# XTIDA-010086_Bias_Power_Supply.net
KiCad netlist of a schematic drawn in Altium Designer
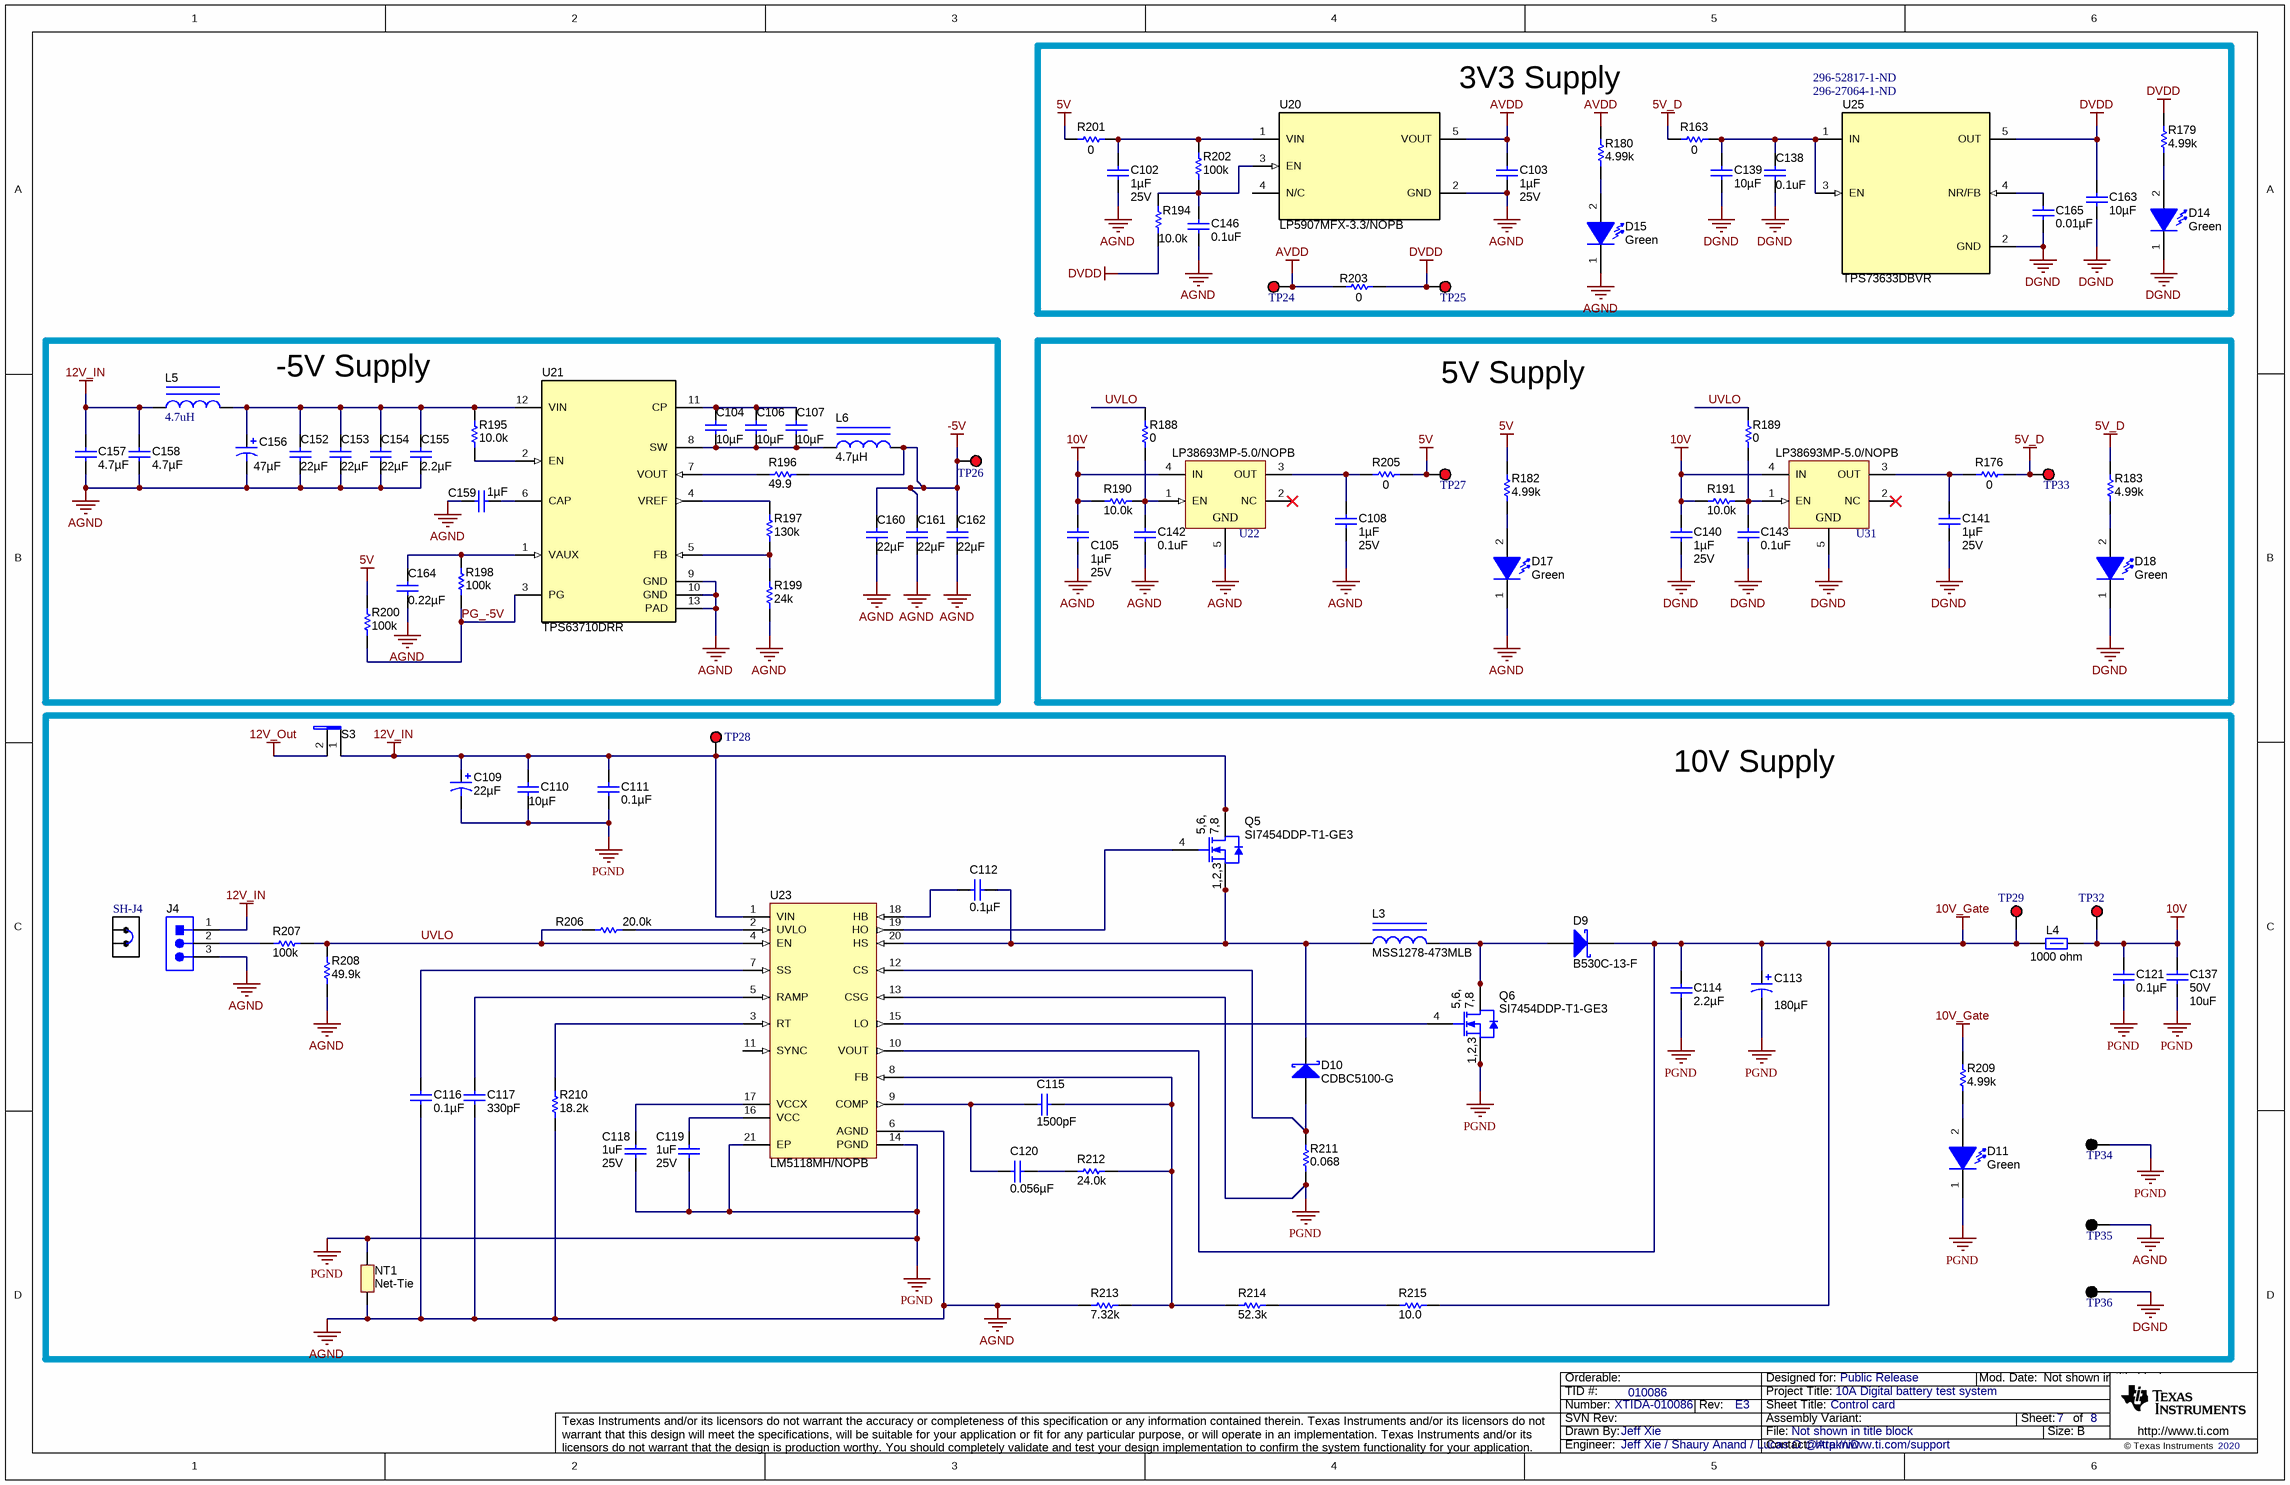
[diagram p0: XTIDA-010086_Bias Power Supply.SchDoc]

(export (version "E")
  (design (tool "Eeschema 10.0.6"))
  (components
    (comp (ref "C102")
      (value "GRM188R71E105KA12D")
      (footprint "0603")
      (description "CAP, CERM, 1 uF, 25 V, +/- 10%, X7R, 0603")
      (fields
        (field (name "MANUFACTURER") "MuRata")
        (field (name "CAP_F") "1µF")
        (field (name "VDC_V") "25V")
        (field (name "PUBLISHER") "Texas Instruments")
      )
      (libsource (lib "Capacitor_Ceramic") (part "Capacitor"))
    )
    (comp (ref "C103")
      (value "GRM188R71E105KA12D")
      (footprint "0603")
      (description "CAP, CERM, 1 uF, 25 V, +/- 10%, X7R, 0603")
      (fields
        (field (name "MANUFACTURER") "MuRata")
        (field (name "CAP_F") "1µF")
        (field (name "VDC_V") "25V")
        (field (name "PUBLISHER") "Texas Instruments")
      )
      (libsource (lib "Capacitor_Ceramic") (part "Capacitor"))
    )
    (comp (ref "C104")
      (value "EMK212BB7106MG-T")
      (footprint "0805_HV1")
      (description "CAP, CERM, 10 µF, 16 V, +/- 20%, X7R, 0805")
      (fields
        (field (name "VALUEDISPLAYED") "10µF")
        (field (name "MANUFACTURER") "Taiyo Yuden")
        (field (name "PUBLISHER") "Texas Instruments")
      )
      (libsource (lib "Capacitor_Ceramic") (part "EMK212BB7106MG-T"))
    )
    (comp (ref "C105")
      (value "GRM188R71E105KA12D")
      (footprint "0603")
      (description "CAP, CERM, 1 uF, 25 V, +/- 10%, X7R, 0603")
      (fields
        (field (name "MANUFACTURER") "MuRata")
        (field (name "CAP_F") "1µF")
        (field (name "VDC_V") "25V")
        (field (name "PUBLISHER") "Texas Instruments")
      )
      (libsource (lib "Capacitor_Ceramic") (part "Capacitor"))
    )
    (comp (ref "C106")
      (value "EMK212BB7106MG-T")
      (footprint "0805_HV1")
      (description "CAP, CERM, 10 µF, 16 V, +/- 20%, X7R, 0805")
      (fields
        (field (name "VALUEDISPLAYED") "10µF")
        (field (name "MANUFACTURER") "Taiyo Yuden")
        (field (name "PUBLISHER") "Texas Instruments")
      )
      (libsource (lib "Capacitor_Ceramic") (part "EMK212BB7106MG-T"))
    )
    (comp (ref "C107")
      (value "EMK212BB7106MG-T")
      (footprint "0805_HV1")
      (description "CAP, CERM, 10 µF, 16 V, +/- 20%, X7R, 0805")
      (fields
        (field (name "VALUEDISPLAYED") "10µF")
        (field (name "MANUFACTURER") "Taiyo Yuden")
        (field (name "PUBLISHER") "Texas Instruments")
      )
      (libsource (lib "Capacitor_Ceramic") (part "EMK212BB7106MG-T"))
    )
    (comp (ref "C108")
      (value "GRM188R71E105KA12D")
      (footprint "0603")
      (description "CAP, CERM, 1 uF, 25 V, +/- 10%, X7R, 0603")
      (fields
        (field (name "MANUFACTURER") "MuRata")
        (field (name "CAP_F") "1µF")
        (field (name "VDC_V") "25V")
        (field (name "PUBLISHER") "Texas Instruments")
      )
      (libsource (lib "Capacitor_Ceramic") (part "Capacitor"))
    )
    (comp (ref "C109")
      (value "EMVH101ADA220MJA0G")
      (footprint "CAPSMT_62_JA0")
      (description "CAP, AL, 22 µF, 100 V, +/- 20%, 0.55 ohm, SMD")
      (fields
        (field (name "VALUEDISPLAYED") "22µF")
        (field (name "MANUFACTURER") "Chemi-Con")
        (field (name "PUBLISHER") "Texas Instruments")
      )
      (libsource (lib "Capacitor_Aluminum") (part "EMVH101ADA220MJA0G"))
    )
    (comp (ref "C110")
      (value "C5750X7S2A106M230KB")
      (footprint "2220_250")
      (description "CAP, CERM, 10 µF, 100 V, +/- 20%, X7S,")
      (fields
        (field (name "VALUEDISPLAYED") "10µF")
        (field (name "MANUFACTURER") "TDK")
        (field (name "PUBLISHER") "Texas Instruments")
      )
      (libsource (lib "Capacitor_Ceramic") (part "C5750X7S2A106M230KB"))
    )
    (comp (ref "C111")
      (value "C2012X7R2A104K125AA")
      (footprint "0805_HV")
      (description "CAP, CERM, 0.1 µF, 100 V, +/- 10%, X7R, 0805")
      (fields
        (field (name "VALUEDISPLAYED") "0.1µF")
        (field (name "MANUFACTURER") "TDK")
        (field (name "PUBLISHER") "Texas Instruments")
      )
      (libsource (lib "Capacitor_Ceramic") (part "C2012X7R2A104K125AA"))
    )
    (comp (ref "C112")
      (value "GRM188R72A104KA35D")
      (footprint "0603L")
      (description "CAP, CERM, 0.1 µF, 100 V, +/- 10%, X7R, 0603")
      (fields
        (field (name "VALUEDISPLAYED") "0.1µF")
        (field (name "MANUFACTURER") "MuRata")
        (field (name "PUBLISHER") "Texas Instruments")
      )
      (libsource (lib "Capacitor_Ceramic") (part "GRM188R72A104KA35D"))
    )
    (comp (ref "C113")
      (value "APXA160ARA181MHC0G")
      (footprint "CAPSMT_62_HC0")
      (description "CAP, Aluminum Polymer, 180 µF, 16 V, +/- 20%, 0.016 ohm, HC0 SMD")
      (fields
        (field (name "VALUEDISPLAYED") "180µF")
        (field (name "MANUFACTURER") "Chemi-Con")
        (field (name "PUBLISHER") "Texas Instruments")
      )
      (libsource (lib "Capacitor_Other") (part "APXA160ARA181MHC0G"))
    )
    (comp (ref "C114")
      (value "C2012X7R1C225K125AB")
      (footprint "0805_HV")
      (description "CAP, CERM, 2.2 µF, 16 V, +/- 10%, X7R, 0805")
      (fields
        (field (name "VALUEDISPLAYED") "2.2µF")
        (field (name "MANUFACTURER") "TDK")
        (field (name "PUBLISHER") "Texas Instruments")
      )
      (libsource (lib "Capacitor_Ceramic") (part "C2012X7R1C225K125AB"))
    )
    (comp (ref "C115")
      (value "GRM1885C2A152JA01D")
      (footprint "0603L")
      (description "CAP, CERM, 1500 pF, 100 V, +/- 5%, C0G/NP0, 0603")
      (fields
        (field (name "VALUEDISPLAYED") "1500pF")
        (field (name "MANUFACTURER") "MuRata")
        (field (name "PUBLISHER") "Texas Instruments")
      )
      (libsource (lib "Capacitor_Ceramic") (part "GRM1885C2A152JA01D"))
    )
    (comp (ref "C116")
      (value "GRM188R72A104KA35D")
      (footprint "0603L")
      (description "CAP, CERM, 0.1 µF, 100 V, +/- 10%, X7R, 0603")
      (fields
        (field (name "VALUEDISPLAYED") "0.1µF")
        (field (name "MANUFACTURER") "MuRata")
        (field (name "PUBLISHER") "Texas Instruments")
      )
      (libsource (lib "Capacitor_Ceramic") (part "GRM188R72A104KA35D"))
    )
    (comp (ref "C117")
      (value "C1608C0G2A331J080AA")
      (footprint "0603L")
      (description "CAP, CERM, 330 pF, 100 V, +/- 5%, C0G/NP0, 0603")
      (fields
        (field (name "VALUEDISPLAYED") "330pF")
        (field (name "MANUFACTURER") "TDK")
        (field (name "PUBLISHER") "Texas Instruments")
      )
      (libsource (lib "Capacitor_Ceramic") (part "C1608C0G2A331J080AA"))
    )
    (comp (ref "C118")
      (value "GRM188R71E105KA12D")
      (footprint "0603")
      (description "CAP, CERM, 1 uF, 25 V, +/- 10%, X7R, 0603")
      (fields
        (field (name "VALUEDISPLAYED") "1uF")
        (field (name "MANUFACTURER") "MuRata")
        (field (name "VDC_V") "25V")
        (field (name "PUBLISHER") "Texas Instruments")
      )
      (libsource (lib "Capacitor_Ceramic") (part "Capacitor"))
    )
    (comp (ref "C119")
      (value "GRM188R71E105KA12D")
      (footprint "0603")
      (description "CAP, CERM, 1 uF, 25 V, +/- 10%, X7R, 0603")
      (fields
        (field (name "VALUEDISPLAYED") "1uF")
        (field (name "MANUFACTURER") "MuRata")
        (field (name "VDC_V") "25V")
        (field (name "PUBLISHER") "Texas Instruments")
      )
      (libsource (lib "Capacitor_Ceramic") (part "Capacitor"))
    )
    (comp (ref "C120")
      (value "GRM188R71H563KA93D")
      (footprint "0603L")
      (description "CAP, CERM, 0.056 µF, 50 V, +/- 10%, X7R, 0603")
      (fields
        (field (name "VALUEDISPLAYED") "0.056µF")
        (field (name "MANUFACTURER") "MuRata")
        (field (name "PUBLISHER") "Texas Instruments")
      )
      (libsource (lib "Capacitor_Ceramic") (part "GRM188R71H563KA93D"))
    )
    (comp (ref "C121")
      (value "C2012X7R2A104K125AA")
      (footprint "0805_HV")
      (description "CAP, CERM, 0.1 µF, 100 V, +/- 10%, X7R, 0805")
      (fields
        (field (name "VALUEDISPLAYED") "0.1µF")
        (field (name "MANUFACTURER") "TDK")
        (field (name "PUBLISHER") "Texas Instruments")
      )
      (libsource (lib "Capacitor_Ceramic") (part "C2012X7R2A104K125AA"))
    )
    (comp (ref "C137")
      (value "C3225X7R1H106M250AC")
      (footprint "1210_280")
      (description "CAP, CERM, 10 uF, 50 V, +/- 20%, X7R, 1210")
      (fields
        (field (name "MANUFACTURER") "TDK")
        (field (name "VDC_V") "50V")
        (field (name "VALUEDISPLAYED") "10uF")
        (field (name "PUBLISHER") "Texas Instruments")
      )
      (libsource (lib "TIDA-010086") (part "Capacitor"))
    )
    (comp (ref "C138")
      (value "06033C104JAT2A")
      (footprint "0603")
      (description "CAP, CERM, 0.1 uF, 25 V, +/- 5%, X7R, 0603")
      (fields
        (field (name "VALUEDISPLAYED") "0.1uF")
        (field (name "MANUFACTURER") "AVX")
        (field (name "PUBLISHER") "Texas Instruments")
      )
      (libsource (lib "TIDA-010086") (part "Capacitor"))
    )
    (comp (ref "C139")
      (value "GRM188R61E106MA73D")
      (footprint "0603")
      (description "CAP, CERM, 10 µF, 25 V,+/- 20%, X5R, 0603")
      (fields
        (field (name "VALUEDISPLAYED") "10µF")
        (field (name "MANUFACTURER") "MuRata")
        (field (name "PUBLISHER") "Texas Instruments")
      )
      (libsource (lib "Capacitor_Ceramic") (part "GRM188R61E106MA73D"))
    )
    (comp (ref "C140")
      (value "GRM188R71E105KA12D")
      (footprint "0603")
      (description "CAP, CERM, 1 uF, 25 V, +/- 10%, X7R, 0603")
      (fields
        (field (name "MANUFACTURER") "MuRata")
        (field (name "CAP_F") "1µF")
        (field (name "VDC_V") "25V")
        (field (name "PUBLISHER") "Texas Instruments")
      )
      (libsource (lib "Capacitor_Ceramic") (part "Capacitor"))
    )
    (comp (ref "C141")
      (value "GRM188R71E105KA12D")
      (footprint "0603")
      (description "CAP, CERM, 1 uF, 25 V, +/- 10%, X7R, 0603")
      (fields
        (field (name "MANUFACTURER") "MuRata")
        (field (name "CAP_F") "1µF")
        (field (name "VDC_V") "25V")
        (field (name "PUBLISHER") "Texas Instruments")
      )
      (libsource (lib "Capacitor_Ceramic") (part "Capacitor"))
    )
    (comp (ref "C142")
      (value "06033C104JAT2A")
      (footprint "0603")
      (description "CAP, CERM, 0.1 uF, 25 V, +/- 5%, X7R, 0603")
      (fields
        (field (name "VALUEDISPLAYED") "0.1uF")
        (field (name "MANUFACTURER") "AVX")
        (field (name "PUBLISHER") "Texas Instruments")
      )
      (libsource (lib "TIDA-010086") (part "Capacitor"))
    )
    (comp (ref "C143")
      (value "06033C104JAT2A")
      (footprint "0603")
      (description "CAP, CERM, 0.1 uF, 25 V, +/- 5%, X7R, 0603")
      (fields
        (field (name "VALUEDISPLAYED") "0.1uF")
        (field (name "MANUFACTURER") "AVX")
        (field (name "PUBLISHER") "Texas Instruments")
      )
      (libsource (lib "TIDA-010086") (part "Capacitor"))
    )
    (comp (ref "C146")
      (value "06033C104JAT2A")
      (footprint "0603")
      (description "CAP, CERM, 0.1 uF, 25 V, +/- 5%, X7R, 0603")
      (fields
        (field (name "VALUEDISPLAYED") "0.1uF")
        (field (name "MANUFACTURER") "AVX")
        (field (name "PUBLISHER") "Texas Instruments")
      )
      (libsource (lib "TIDA-010086") (part "Capacitor"))
    )
    (comp (ref "C152")
      (value "EMK316BB7226ML-T")
      (footprint "1206_190")
      (description "CAP, CERM, 22 µF, 16 V, +/- 20%, X7R, 1206_190")
      (fields
        (field (name "VALUEDISPLAYED") "22µF")
        (field (name "MANUFACTURER") "Taiyo Yuden")
        (field (name "PUBLISHER") "Texas Instruments")
      )
      (libsource (lib "Capacitor_Ceramic") (part "EMK316BB7226ML-T"))
    )
    (comp (ref "C153")
      (value "EMK316BB7226ML-T")
      (footprint "1206_190")
      (description "CAP, CERM, 22 µF, 16 V, +/- 20%, X7R, 1206_190")
      (fields
        (field (name "VALUEDISPLAYED") "22µF")
        (field (name "MANUFACTURER") "Taiyo Yuden")
        (field (name "PUBLISHER") "Texas Instruments")
      )
      (libsource (lib "Capacitor_Ceramic") (part "EMK316BB7226ML-T"))
    )
    (comp (ref "C154")
      (value "EMK316BB7226ML-T")
      (footprint "1206_190")
      (description "CAP, CERM, 22 µF, 16 V, +/- 20%, X7R, 1206_190")
      (fields
        (field (name "VALUEDISPLAYED") "22µF")
        (field (name "MANUFACTURER") "Taiyo Yuden")
        (field (name "PUBLISHER") "Texas Instruments")
      )
      (libsource (lib "Capacitor_Ceramic") (part "EMK316BB7226ML-T"))
    )
    (comp (ref "C155")
      (value "EMK107BB7225KA-T")
      (footprint "0603_HV")
      (description "CAP, CERM, 2.2 µF, 16 V, +/- 10%, X7R, 0603")
      (fields
        (field (name "VALUEDISPLAYED") "2.2µF")
        (field (name "MANUFACTURER") "Taiyo Yuden")
        (field (name "PUBLISHER") "Texas Instruments")
      )
      (libsource (lib "Capacitor_Ceramic") (part "EMK107BB7225KA-T"))
    )
    (comp (ref "C156")
      (value "F951C476MBAAQ2")
      (footprint "F95_B")
      (description "CAP, TA, 47 µF, 16 V, +/- 20%, 0.6 ohm, SMD")
      (fields
        (field (name "VALUEDISPLAYED") "47µF")
        (field (name "MANUFACTURER") "AVX")
        (field (name "PUBLISHER") "Texas Instruments")
      )
      (libsource (lib "Capacitor_Tantalum") (part "F951C476MBAAQ2"))
    )
    (comp (ref "C157")
      (value "GRM319R61E475KA12D")
      (footprint "1206")
      (description "CAP, CERM, 4.7 µF, 25 V,+/- 10%, X5R, 1206")
      (fields
        (field (name "VALUEDISPLAYED") "4.7µF")
        (field (name "MANUFACTURER") "MuRata")
        (field (name "PUBLISHER") "Texas Instruments")
      )
      (libsource (lib "Capacitor_Ceramic") (part "GRM319R61E475KA12D"))
    )
    (comp (ref "C158")
      (value "GRM319R61E475KA12D")
      (footprint "1206")
      (description "CAP, CERM, 4.7 µF, 25 V,+/- 10%, X5R, 1206")
      (fields
        (field (name "VALUEDISPLAYED") "4.7µF")
        (field (name "MANUFACTURER") "MuRata")
        (field (name "PUBLISHER") "Texas Instruments")
      )
      (libsource (lib "Capacitor_Ceramic") (part "GRM319R61E475KA12D"))
    )
    (comp (ref "C159")
      (value "C1005X5R1C105K050BC")
      (footprint "0402")
      (description "CAP, CERM, 1 µF, 16 V,+/- 10%, X5R, 0402")
      (fields
        (field (name "VALUEDISPLAYED") "1µF")
        (field (name "MANUFACTURER") "TDK")
        (field (name "PUBLISHER") "Texas Instruments")
      )
      (libsource (lib "Capacitor_Ceramic") (part "C1005X5R1C105K050BC"))
    )
    (comp (ref "C160")
      (value "C2012X7S1A226M125AC")
      (footprint "0805_HV1")
      (description "CAP, CERM, 22 µF, 10 V, +/- 20%, X7S, 0805")
      (fields
        (field (name "VALUEDISPLAYED") "22µF")
        (field (name "MANUFACTURER") "TDK")
        (field (name "PUBLISHER") "Texas Instruments")
      )
      (libsource (lib "Capacitor_Ceramic") (part "C2012X7S1A226M125AC"))
    )
    (comp (ref "C161")
      (value "C2012X7S1A226M125AC")
      (footprint "0805_HV1")
      (description "CAP, CERM, 22 µF, 10 V, +/- 20%, X7S, 0805")
      (fields
        (field (name "VALUEDISPLAYED") "22µF")
        (field (name "MANUFACTURER") "TDK")
        (field (name "PUBLISHER") "Texas Instruments")
      )
      (libsource (lib "Capacitor_Ceramic") (part "C2012X7S1A226M125AC"))
    )
    (comp (ref "C162")
      (value "C2012X7S1A226M125AC")
      (footprint "0805_HV1")
      (description "CAP, CERM, 22 µF, 10 V, +/- 20%, X7S, 0805")
      (fields
        (field (name "VALUEDISPLAYED") "22µF")
        (field (name "MANUFACTURER") "TDK")
        (field (name "PUBLISHER") "Texas Instruments")
      )
      (libsource (lib "Capacitor_Ceramic") (part "C2012X7S1A226M125AC"))
    )
    (comp (ref "C163")
      (value "GRM188R61E106MA73D")
      (footprint "0603")
      (description "CAP, CERM, 10 µF, 25 V,+/- 20%, X5R, 0603")
      (fields
        (field (name "VALUEDISPLAYED") "10µF")
        (field (name "MANUFACTURER") "MuRata")
        (field (name "PUBLISHER") "Texas Instruments")
      )
      (libsource (lib "Capacitor_Ceramic") (part "GRM188R61E106MA73D"))
    )
    (comp (ref "C164")
      (value "GRM155R71C224KA12D")
      (footprint "0402")
      (description "CAP, CERM, 0.22 µF, 16 V,+/- 10%, X7R, 0402")
      (fields
        (field (name "VALUEDISPLAYED") "0.22µF")
        (field (name "MANUFACTURER") "MuRata")
        (field (name "PUBLISHER") "Texas Instruments")
      )
      (libsource (lib "Capacitor_Ceramic") (part "GRM155R71C224KA12D"))
    )
    (comp (ref "C165")
      (value "06031C103KAT2A")
      (footprint "0603")
      (description "CAP, CERM, 0.01 µF, 100 V, +/- 10%, X7R, 0603")
      (fields
        (field (name "VALUEDISPLAYED") "0.01µF")
        (field (name "MANUFACTURER") "AVX")
        (field (name "PUBLISHER") "Texas Instruments")
      )
      (libsource (lib "Capacitor_Ceramic") (part "06031C103KAT2A"))
    )
    (comp (ref "D9")
      (value "B530C-13-F")
      (footprint "SMC")
      (description "Diode, Schottky, 30 V, 5 A, SMC")
      (fields (field (name "MANUFACTURER") "Diodes Inc.") (field (name "PUBLISHER") "Texas Instruments"))
      (libsource (lib "Diode") (part "B530C-13-F"))
    )
    (comp (ref "D10")
      (value "CDBC5100-G")
      (footprint "SMC")
      (description "Diode, Schottky, 100 V, 5 A, SMC")
      (fields
        (field (name "MANUFACTURER") "Comchip Technology")
        (field (name "PUBLISHER") "Texas Instruments")
      )
      (libsource (lib "Diode") (part "CDBC5100-G"))
    )
    (comp (ref "D11")
      (value "Green")
      (footprint "WL-SMCW_GREEN")
      (description "LED, Green, SMD")
      (fields
        (field (name "MANUFACTURER") "Wurth Elektronik")
        (field (name "PARTNUMBER") "150060VS75000")
        (field (name "PUBLISHER") "Texas Instruments")
      )
      (libsource (lib "LED") (part "150060VS75000"))
    )
    (comp (ref "D14")
      (value "Green")
      (footprint "WL-SMCW_GREEN")
      (description "LED, Green, SMD")
      (fields
        (field (name "MANUFACTURER") "Wurth Elektronik")
        (field (name "PARTNUMBER") "150060VS75000")
        (field (name "PUBLISHER") "Texas Instruments")
      )
      (libsource (lib "LED") (part "150060VS75000"))
    )
    (comp (ref "D15")
      (value "Green")
      (footprint "WL-SMCW_GREEN")
      (description "LED, Green, SMD")
      (fields
        (field (name "MANUFACTURER") "Wurth Elektronik")
        (field (name "PARTNUMBER") "150060VS75000")
        (field (name "PUBLISHER") "Texas Instruments")
      )
      (libsource (lib "LED") (part "150060VS75000"))
    )
    (comp (ref "D17")
      (value "Green")
      (footprint "WL-SMCW_GREEN")
      (description "LED, Green, SMD")
      (fields
        (field (name "MANUFACTURER") "Wurth Elektronik")
        (field (name "PARTNUMBER") "150060VS75000")
        (field (name "PUBLISHER") "Texas Instruments")
      )
      (libsource (lib "LED") (part "150060VS75000"))
    )
    (comp (ref "D18")
      (value "Green")
      (footprint "WL-SMCW_GREEN")
      (description "LED, Green, SMD")
      (fields
        (field (name "MANUFACTURER") "Wurth Elektronik")
        (field (name "PARTNUMBER") "150060VS75000")
        (field (name "PUBLISHER") "Texas Instruments")
      )
      (libsource (lib "LED") (part "150060VS75000"))
    )
    (comp (ref "J4")
      (value "0022284033")
      (footprint "Molex_0022284033")
      (description "Header, 2.54mm, 3x1, Tin, TH")
      (fields
        (field (name "MANUFACTURER") "Molex")
        (field (name "SYMBOLCREATOR") "a0799628")
        (field (name "PUBLISHER") "Texas Instruments")
      )
      (libsource (lib "Connectors_Molex") (part "0022284033"))
    )
    (comp (ref "L3")
      (value "MSS1278-473MLB")
      (footprint "mss1278")
      (description "Inductor, Shielded Drum Core, Ferrite, 47 µH, 2.9 A, 0.07 ohm, SMD")
      (fields (field (name "MANUFACTURER") "Coilcraft") (field (name "PUBLISHER") "Texas Instruments"))
      (libsource (lib "TIDA-010086") (part "MSS1278-473MLB"))
    )
    (comp (ref "L4")
      (value "1000 ohm")
      (footprint "1806_HighSpeed")
      (description "Ferrite Bead, 1000 ohm @ 100 MHz, 1.5 A, 1806")
      (fields
        (field (name "MANUFACTURER") "MuRata")
        (field (name "PARTNUMBER") "BLM41PG102SN1L")
        (field (name "PUBLISHER") "Texas Instruments")
      )
      (libsource (lib "TIDA-010086") (part "CMP-0003369-1"))
    )
    (comp (ref "L5")
      (value "MAKK2016T4R7M")
      (footprint "MAKK2016")
      (description "Inductor, Wirewound, 4.7 uH, 0.95 A, 0.38 ohm, SMD")
      (fields
        (field (name "MANUFACTURER") "Taiyo Yuden")
        (field (name "VALUEDISPLAYED") "4.7uH")
        (field (name "PUBLISHER") "Texas Instruments")
      )
      (libsource (lib "TIDA-010086") (part "Inductor_Iron"))
    )
    (comp (ref "L6")
      (value "XFL4020-472MEB")
      (footprint "XFL4020")
      (description "Inductor, Shielded, Composite, 4.7 µH, 2.7 A, 0.05 ohm, SMD")
      (fields
        (field (name "VALUEDISPLAYED") "4.7µH")
        (field (name "MANUFACTURER") "Coilcraft")
        (field (name "PUBLISHER") "Texas Instruments")
      )
      (libsource (lib "TIDA-010086") (part "XFL4020-472MEB"))
    )
    (comp (ref "NT1")
      (value "Net-Tie")
      (footprint "Net-Tie_10mil")
      (description "Single point connection between nets.")
      (fields (field (name "SYMBOLCREATOR") "codlsc") (field (name "PUBLISHER") "Texas Instruments"))
      (libsource (lib "MiscParts") (part "Net-Tie"))
    )
    (comp (ref "Q5")
      (value "SI7454DDP-T1-GE3")
      (footprint "PowerPAK_SO-8")
      (description "MOSFET, N-CH, 100 V, 21 A, PowerPAK SO-8")
      (fields (field (name "MANUFACTURER") "Vishay-Siliconix") (field (name "PUBLISHER") "Texas Instruments"))
      (libsource (lib "FETs") (part "SI7454DDP-T1-GE3"))
    )
    (comp (ref "Q6")
      (value "SI7454DDP-T1-GE3")
      (footprint "PowerPAK_SO-8")
      (description "MOSFET, N-CH, 100 V, 21 A, PowerPAK SO-8")
      (fields (field (name "MANUFACTURER") "Vishay-Siliconix") (field (name "PUBLISHER") "Texas Instruments"))
      (libsource (lib "FETs") (part "SI7454DDP-T1-GE3"))
    )
    (comp (ref "R163")
      (value "CRCW06030000Z0ED")
      (footprint "0603")
      (description "RES, 0, 5%, 0.1 W, 0603")
      (fields
        (field (name "PARTNUMBER") "ERJ-3GEY0R00V")
        (field (name "MANUFACTURER") "Panasonic")
        (field (name "VALUEDISPLAYED") "0")
        (field (name "PUBLISHER") "Texas Instruments")
      )
      (libsource (lib "TIDA-010086") (part "CMP-0025874-3"))
    )
    (comp (ref "R176")
      (value "CRCW06030000Z0ED")
      (footprint "0603")
      (description "RES, 0, 5%, 0.1 W, 0603")
      (fields
        (field (name "PARTNUMBER") "ERJ-3GEY0R00V")
        (field (name "MANUFACTURER") "Panasonic")
        (field (name "VALUEDISPLAYED") "0")
        (field (name "PUBLISHER") "Texas Instruments")
      )
      (libsource (lib "TIDA-010086") (part "CMP-0025874-3"))
    )
    (comp (ref "R179")
      (value "CRCW06034K99FKEA")
      (footprint "0603L")
      (description "RES, 4.99 k, 1%, 0.1 W, 0603")
      (fields
        (field (name "VALUEDISPLAYED") "4.99k")
        (field (name "MANUFACTURER") "Vishay-Dale")
        (field (name "PUBLISHER") "Texas Instruments")
      )
      (libsource (lib "Resistor_0603") (part "CRCW06034K99FKEA"))
    )
    (comp (ref "R180")
      (value "CRCW06034K99FKEA")
      (footprint "0603L")
      (description "RES, 4.99 k, 1%, 0.1 W, 0603")
      (fields
        (field (name "VALUEDISPLAYED") "4.99k")
        (field (name "MANUFACTURER") "Vishay-Dale")
        (field (name "PUBLISHER") "Texas Instruments")
      )
      (libsource (lib "Resistor_0603") (part "CRCW06034K99FKEA"))
    )
    (comp (ref "R182")
      (value "CRCW06034K99FKEA")
      (footprint "0603L")
      (description "RES, 4.99 k, 1%, 0.1 W, 0603")
      (fields
        (field (name "VALUEDISPLAYED") "4.99k")
        (field (name "MANUFACTURER") "Vishay-Dale")
        (field (name "PUBLISHER") "Texas Instruments")
      )
      (libsource (lib "Resistor_0603") (part "CRCW06034K99FKEA"))
    )
    (comp (ref "R183")
      (value "CRCW06034K99FKEA")
      (footprint "0603L")
      (description "RES, 4.99 k, 1%, 0.1 W, 0603")
      (fields
        (field (name "VALUEDISPLAYED") "4.99k")
        (field (name "MANUFACTURER") "Vishay-Dale")
        (field (name "PUBLISHER") "Texas Instruments")
      )
      (libsource (lib "Resistor_0603") (part "CRCW06034K99FKEA"))
    )
    (comp (ref "R188")
      (value "CRCW04020000Z0ED")
      (footprint "0402")
      (description "RES, 0, 5%, 0.063 W, 0402")
      (fields
        (field (name "VALUEDISPLAYED") "0")
        (field (name "MANUFACTURER") "Vishay-Dale")
        (field (name "PUBLISHER") "Texas Instruments")
      )
      (libsource (lib "Resistor_0402") (part "CRCW04020000Z0ED"))
    )
    (comp (ref "R189")
      (value "CRCW04020000Z0ED")
      (footprint "0402")
      (description "RES, 0, 5%, 0.063 W, 0402")
      (fields
        (field (name "VALUEDISPLAYED") "0")
        (field (name "MANUFACTURER") "Vishay-Dale")
        (field (name "PUBLISHER") "Texas Instruments")
      )
      (libsource (lib "Resistor_0402") (part "CRCW04020000Z0ED"))
    )
    (comp (ref "R190")
      (value "RC0603FR-0710KL")
      (footprint "0603")
      (description "RES, 10.0 k, 1%, 0.1 W, 0603")
      (fields (field (name "MANUFACTURER") "Yageo") (field (name "VALUEDISPLAYED") "10.0k"))
      (libsource (lib "TIDA-010086") (part "Resistor"))
    )
    (comp (ref "R191")
      (value "RC0603FR-0710KL")
      (footprint "0603")
      (description "RES, 10.0 k, 1%, 0.1 W, 0603")
      (fields (field (name "MANUFACTURER") "Yageo") (field (name "VALUEDISPLAYED") "10.0k"))
      (libsource (lib "TIDA-010086") (part "Resistor"))
    )
    (comp (ref "R194")
      (value "RC0603FR-0710KL")
      (footprint "0603")
      (description "RES, 10.0 k, 1%, 0.1 W, 0603")
      (fields (field (name "MANUFACTURER") "Yageo") (field (name "VALUEDISPLAYED") "10.0k"))
      (libsource (lib "TIDA-010086") (part "Resistor"))
    )
    (comp (ref "R195")
      (value "RC0603FR-0710KL")
      (footprint "0603")
      (description "RES, 10.0 k, 1%, 0.1 W, 0603")
      (fields (field (name "MANUFACTURER") "Yageo") (field (name "VALUEDISPLAYED") "10.0k"))
      (libsource (lib "TIDA-010086") (part "Resistor"))
    )
    (comp (ref "R196")
      (value "CRCW040249R9FKED")
      (footprint "0402")
      (description "RES, 49.9, 1%, 0.063 W, 0402")
      (fields
        (field (name "VALUEDISPLAYED") "49.9")
        (field (name "MANUFACTURER") "Vishay-Dale")
        (field (name "PUBLISHER") "Texas Instruments")
      )
      (libsource (lib "Resistor_0402") (part "CRCW040249R9FKED"))
    )
    (comp (ref "R197")
      (value "CRCW0402130KFKED")
      (footprint "0402")
      (description "RES, 130 k, 1%, 0.063 W, 0402")
      (fields
        (field (name "VALUEDISPLAYED") "130k")
        (field (name "MANUFACTURER") "Vishay-Dale")
        (field (name "PUBLISHER") "Texas Instruments")
      )
      (libsource (lib "Resistor_0402") (part "CRCW0402130KFKED"))
    )
    (comp (ref "R198")
      (value "CRCW0402100KDHEDP")
      (footprint "0402")
      (description "RES, 100 k, 0.5%, 0.063 W, 0402")
      (fields
        (field (name "VALUEDISPLAYED") "100k")
        (field (name "MANUFACTURER") "Vishay-Dale")
        (field (name "PUBLISHER") "Texas Instruments")
      )
      (libsource (lib "Resistor_0402") (part "CRCW0402100KDHEDP"))
    )
    (comp (ref "R199")
      (value "CRCW040224K0JNED")
      (footprint "0402")
      (description "RES, 24 k, 5%, 0.063 W, 0402")
      (fields
        (field (name "VALUEDISPLAYED") "24k")
        (field (name "MANUFACTURER") "Vishay-Dale")
        (field (name "PUBLISHER") "Texas Instruments")
      )
      (libsource (lib "Resistor_0402") (part "CRCW040224K0JNED"))
    )
    (comp (ref "R200")
      (value "CRCW0402100KDHEDP")
      (footprint "0402")
      (description "RES, 100 k, 0.5%, 0.063 W, 0402")
      (fields
        (field (name "VALUEDISPLAYED") "100k")
        (field (name "MANUFACTURER") "Vishay-Dale")
        (field (name "PUBLISHER") "Texas Instruments")
      )
      (libsource (lib "Resistor_0402") (part "CRCW0402100KDHEDP"))
    )
    (comp (ref "R201")
      (value "CRCW06030000Z0ED")
      (footprint "0603")
      (description "RES, 0, 5%, 0.1 W, 0603")
      (fields
        (field (name "PARTNUMBER") "ERJ-3GEY0R00V")
        (field (name "MANUFACTURER") "Panasonic")
        (field (name "VALUEDISPLAYED") "0")
        (field (name "PUBLISHER") "Texas Instruments")
      )
      (libsource (lib "TIDA-010086") (part "CMP-0025874-3"))
    )
    (comp (ref "R202")
      (value "CRCW0603100KFKEA")
      (footprint "0603")
      (description "RES, 100 k, 1%, 0.1 W, 0603")
      (fields
        (field (name "MANUFACTURER") "Vishay-Dale")
        (field (name "VALUEDISPLAYED") "100k")
        (field (name "PUBLISHER") "Texas Instruments")
      )
      (libsource (lib "TIDA-010086") (part "Resistor"))
    )
    (comp (ref "R203")
      (value "CRCW06030000Z0ED")
      (footprint "0603")
      (description "RES, 0, 5%, 0.1 W, 0603")
      (fields
        (field (name "PARTNUMBER") "ERJ-3GEY0R00V")
        (field (name "MANUFACTURER") "Panasonic")
        (field (name "VALUEDISPLAYED") "0")
        (field (name "PUBLISHER") "Texas Instruments")
      )
      (libsource (lib "TIDA-010086") (part "CMP-0025874-3"))
    )
    (comp (ref "R205")
      (value "CRCW06030000Z0ED")
      (footprint "0603")
      (description "RES, 0, 5%, 0.1 W, 0603")
      (fields
        (field (name "PARTNUMBER") "ERJ-3GEY0R00V")
        (field (name "MANUFACTURER") "Panasonic")
        (field (name "VALUEDISPLAYED") "0")
        (field (name "PUBLISHER") "Texas Instruments")
      )
      (libsource (lib "TIDA-010086") (part "CMP-0025874-3"))
    )
    (comp (ref "R206")
      (value "CRCW060320K0FKEA")
      (footprint "0603L")
      (description "RES, 20.0 k, 1%, 0.1 W, 0603")
      (fields
        (field (name "VALUEDISPLAYED") "20.0k")
        (field (name "MANUFACTURER") "Vishay-Dale")
        (field (name "PUBLISHER") "Texas Instruments")
      )
      (libsource (lib "Resistor_0603") (part "CRCW060320K0FKEA"))
    )
    (comp (ref "R207")
      (value "RC0603FR-07100KL")
      (footprint "0603")
      (description "RES, 100 k, 1%, 0.1 W, 0603")
      (fields (field (name "MANUFACTURER") "Yageo") (field (name "VALUEDISPLAYED") "100k"))
      (libsource (lib "TIDA-010086") (part "Resistor"))
    )
    (comp (ref "R208")
      (value "CRCW060349K9FKEA")
      (footprint "0603")
      (description "RES, 49.9 k, 1%, 0.1 W, 0603")
      (fields
        (field (name "VALUEDISPLAYED") "49.9k")
        (field (name "MANUFACTURER") "Vishay-Dale")
        (field (name "PUBLISHER") "Texas Instruments")
      )
      (libsource (lib "Resistor_0603") (part "CRCW060349K9FKEA"))
    )
    (comp (ref "R209")
      (value "CRCW06034K99FKEA")
      (footprint "0603L")
      (description "RES, 4.99 k, 1%, 0.1 W, 0603")
      (fields
        (field (name "VALUEDISPLAYED") "4.99k")
        (field (name "MANUFACTURER") "Vishay-Dale")
        (field (name "PUBLISHER") "Texas Instruments")
      )
      (libsource (lib "Resistor_0603") (part "CRCW06034K99FKEA"))
    )
    (comp (ref "R210")
      (value "CRCW060318K2FKEA")
      (footprint "0603L")
      (description "RES, 18.2 k, 1%, 0.1 W, 0603")
      (fields
        (field (name "VALUEDISPLAYED") "18.2k")
        (field (name "MANUFACTURER") "Vishay-Dale")
        (field (name "PUBLISHER") "Texas Instruments")
      )
      (libsource (lib "Resistor_0603") (part "CRCW060318K2FKEA"))
    )
    (comp (ref "R211")
      (value "PRL1632-R068-F-T1")
      (footprint "0612")
      (description "RES, 0.068, 1%, 1 W, 0612")
      (fields
        (field (name "VALUEDISPLAYED") "0.068")
        (field (name "MANUFACTURER") "Susumu Co Ltd")
        (field (name "PUBLISHER") "Texas Instruments")
      )
      (libsource (lib "Resistor_OtherSMT") (part "PRL1632-R068-F-T1"))
    )
    (comp (ref "R212")
      (value "RC0603FR-0724KL")
      (footprint "0603L")
      (description "RES, 24.0 k, 1%, 0.1 W, 0603")
      (fields
        (field (name "VALUEDISPLAYED") "24.0k")
        (field (name "MANUFACTURER") "Yageo America")
        (field (name "PUBLISHER") "Texas Instruments")
      )
      (libsource (lib "Resistor_0603") (part "RC0603FR-0724KL"))
    )
    (comp (ref "R213")
      (value "RC0603FR-077K32L")
      (footprint "0603")
      (description "RES, 7.32 k, 1%, 0.1 W, 0603")
      (fields
        (field (name "MANUFACTURER") "Yageo America")
        (field (name "VALUEDISPLAYED") "7.32k")
        (field (name "PUBLISHER") "Texas Instruments")
      )
      (libsource (lib "TIDA-010086") (part "CMP-0023278-3"))
    )
    (comp (ref "R214")
      (value "RC0603FR-0752K3L")
      (footprint "0603")
      (description "RES, 52.3 k, 1%, 0.1 W, 0603")
      (fields
        (field (name "MANUFACTURER") "Yageo America")
        (field (name "VALUEDISPLAYED") "52.3k")
        (field (name "PUBLISHER") "Texas Instruments")
      )
      (libsource (lib "TIDA-010086") (part "CMP-0023172-3"))
    )
    (comp (ref "R215")
      (value "CRCW060310R0FKEA")
      (footprint "0603L")
      (description "RES, 10.0, 1%, 0.1 W, 0603")
      (fields
        (field (name "VALUEDISPLAYED") "10.0")
        (field (name "MANUFACTURER") "Vishay-Dale")
        (field (name "PUBLISHER") "Texas Instruments")
      )
      (libsource (lib "Resistor_0603") (part "CRCW060310R0FKEA"))
    )
    (comp (ref "S3")
      (value "L101011MS02Q")
      (footprint "SW_ L101011MS02Q")
      (description "SWITCH SLIDE SPST 4A PCB, TH")
      (fields
        (field (name "MANUFACTURER") "C&K Components")
        (field (name "SYMBOL CREATOR") "a0411947")
        (field (name "PUBLISHER") "Texas Instruments")
      )
      (libsource (lib "Switches") (part "L101011MS02Q"))
    )
    (comp (ref "SH-J4")
      (value "60900213421")
      (footprint "Wurth_60900213421")
      (description "Shunt, 2.54mm, Gold, Black")
      (fields (field (name "MANUFACTURER") "Wurth Elektronik") (field (name "PUBLISHER") "Texas Instruments"))
      (libsource (lib "Hardware") (part "60900213421"))
    )
    (comp (ref "TP24")
      (value "5000")
      (footprint "Keystone5000")
      (description "Test Point, Miniature, Red, TH")
      (fields (field (name "MANUFACTURER") "Keystone") (field (name "PUBLISHER") "Texas Instruments"))
      (libsource (lib "Connectors_Keystone") (part "5000"))
    )
    (comp (ref "TP25")
      (value "5000")
      (footprint "Keystone5000")
      (description "Test Point, Miniature, Red, TH")
      (fields (field (name "MANUFACTURER") "Keystone") (field (name "PUBLISHER") "Texas Instruments"))
      (libsource (lib "Connectors_Keystone") (part "5000"))
    )
    (comp (ref "TP26")
      (value "5000")
      (footprint "Keystone5000")
      (description "Test Point, Miniature, Red, TH")
      (fields (field (name "MANUFACTURER") "Keystone") (field (name "PUBLISHER") "Texas Instruments"))
      (libsource (lib "Connectors_Keystone") (part "5000"))
    )
    (comp (ref "TP27")
      (value "5000")
      (footprint "Keystone5000")
      (description "Test Point, Miniature, Red, TH")
      (fields (field (name "MANUFACTURER") "Keystone") (field (name "PUBLISHER") "Texas Instruments"))
      (libsource (lib "Connectors_Keystone") (part "5000"))
    )
    (comp (ref "TP28")
      (value "5000")
      (footprint "Keystone5000")
      (description "Test Point, Miniature, Red, TH")
      (fields (field (name "MANUFACTURER") "Keystone") (field (name "PUBLISHER") "Texas Instruments"))
      (libsource (lib "Connectors_Keystone") (part "5000"))
    )
    (comp (ref "TP29")
      (value "5000")
      (footprint "Keystone5000")
      (description "Test Point, Miniature, Red, TH")
      (fields (field (name "MANUFACTURER") "Keystone") (field (name "PUBLISHER") "Texas Instruments"))
      (libsource (lib "Connectors_Keystone") (part "5000"))
    )
    (comp (ref "TP32")
      (value "5000")
      (footprint "Keystone5000")
      (description "Test Point, Miniature, Red, TH")
      (fields (field (name "MANUFACTURER") "Keystone") (field (name "PUBLISHER") "Texas Instruments"))
      (libsource (lib "Connectors_Keystone") (part "5000"))
    )
    (comp (ref "TP33")
      (value "5000")
      (footprint "Keystone5000")
      (description "Test Point, Miniature, Red, TH")
      (fields (field (name "MANUFACTURER") "Keystone") (field (name "PUBLISHER") "Texas Instruments"))
      (libsource (lib "Connectors_Keystone") (part "5000"))
    )
    (comp (ref "TP34")
      (value "5001")
      (footprint "Keystone5001")
      (description "Test Point, Miniature, Black, TH")
      (fields (field (name "MANUFACTURER") "Keystone") (field (name "PUBLISHER") "Texas Instruments"))
      (libsource (lib "Connectors_Keystone") (part "5001"))
    )
    (comp (ref "TP35")
      (value "5001")
      (footprint "Keystone5001")
      (description "Test Point, Miniature, Black, TH")
      (fields (field (name "MANUFACTURER") "Keystone") (field (name "PUBLISHER") "Texas Instruments"))
      (libsource (lib "Connectors_Keystone") (part "5001"))
    )
    (comp (ref "TP36")
      (value "5001")
      (footprint "Keystone5001")
      (description "Test Point, Miniature, Black, TH")
      (fields (field (name "MANUFACTURER") "Keystone") (field (name "PUBLISHER") "Texas Instruments"))
      (libsource (lib "Connectors_Keystone") (part "5001"))
    )
    (comp (ref "U20")
      (value "LP5907MFX-3.3/NOPB")
      (footprint "DBV0005A_N")
      (description "250-mA Ultra-Low-Noise, Low-IQ LDO, DBV0005A (SOT-23-5)")
      (fields
        (field (name "MANUFACTURER") "Texas Instruments")
        (field (name "PARTNUMBER") "LP5907MFX-3.3/NOPB")
        (field (name "PUBLISHER") "Texas Instruments")
      )
      (libsource (lib "TIDA-010086") (part "LP5907"))
    )
    (comp (ref "U21")
      (value "TPS63710DRR")
      (footprint "DRR0012C")
      (description "Synchronous Inverting Buck Converter, DRR0012C")
      (fields
        (field (name "MANUFACTURER") "Texas Instruments")
        (field (name "SYMBOLCREATOR") "Altium")
        (field (name "PUBLISHER") "Texas Instruments")
      )
      (libsource (lib "TIDA-010086") (part "TPS63710DRR"))
    )
    (comp (ref "U22")
      (value "LP38693MP-5.0/NOPB")
      (footprint "NDC0005A_N")
      (fields
        (field (name "PARTNUMBER") "LP38693MP-5.0/NOPB")
        (field (name "MANUFACTURER") "Texas Instruments")
      )
      (libsource (lib "TIDA-010086") (part "PM-REG-LP38692-SOT5"))
    )
    (comp (ref "U23")
      (value "LM5118MH/NOPB")
      (footprint "MXA20A_N")
      (description "Wide Voltage Range Buck-Boost Controller, 20-pin TSSOP-EP, Pb-Free")
      (fields (field (name "MANUFACTURER") "Texas Instruments") (field (name "PUBLISHER") "Altium Limited"))
      (libsource (lib "TIDA-010086") (part "LM5118MH/NOPB"))
    )
    (comp (ref "U25")
      (value "TPS73633DBVR")
      (footprint "DBV0005A_N")
      (fields
        (field (name "PARTNUMBER") "TPS73633DBVR")
        (field (name "MANUFACTURER") "Texas Instruments")
        (field (name "ALTERNATE PARTNUMBER") "TPS73633DBVT")
        (field (name "SUPPLIER PART NUMBER 1") "296-27064-1-ND")
        (field (name "SUPPLIER PART NUMBER 2") "296-52817-1-ND")
      )
      (libsource (lib "TIDA-010086") (part "TPS736xxDBV"))
    )
    (comp (ref "U31")
      (value "LP38693MP-5.0/NOPB")
      (footprint "NDC0005A_N")
      (fields
        (field (name "PARTNUMBER") "LP38693MP-5.0/NOPB")
        (field (name "MANUFACTURER") "Texas Instruments")
      )
      (libsource (lib "TIDA-010086") (part "PM-REG-LP38692-SOT5"))
    )
  )
  (nets
    (net (code "1") (name "-5V") (class "Default")
      (node (ref "C160") (pin "1") (pinfunction "1_1") (pintype "passive"))
      (node (ref "C161") (pin "1") (pinfunction "1_1") (pintype "passive"))
      (node (ref "C162") (pin "1") (pinfunction "1_1") (pintype "passive"))
      (node (ref "L6") (pin "2") (pinfunction "2_2") (pintype "passive"))
      (node (ref "R196") (pin "1") (pinfunction "1_1") (pintype "passive"))
      (node (ref "TP26") (pin "1") (pintype "passive"))
    )
    (net (code "2") (name "/PG_-5V") (class "Default")
      (node (ref "R198") (pin "1") (pinfunction "1_1") (pintype "passive"))
      (node (ref "R200") (pin "1") (pinfunction "1_1") (pintype "passive"))
      (node (ref "U21") (pin "3") (pinfunction "PG_3") (pintype "open_collector"))
    )
    (net (code "3") (name "/UVLO") (class "Default")
      (node (ref "R188") (pin "1") (pinfunction "1_1") (pintype "passive"))
      (node (ref "R189") (pin "1") (pinfunction "1_1") (pintype "passive"))
      (node (ref "R206") (pin "1") (pinfunction "1_1") (pintype "passive"))
      (node (ref "R207") (pin "1") (pinfunction "1_1") (pintype "passive"))
      (node (ref "R208") (pin "2") (pinfunction "2_2") (pintype "passive"))
      (node (ref "U23") (pin "4") (pinfunction "EN_4") (pintype "input"))
    )
    (net (code "4") (name "5V") (class "Default")
      (node (ref "R182") (pin "1") (pinfunction "1_1") (pintype "passive"))
      (node (ref "R200") (pin "2") (pinfunction "2_2") (pintype "passive"))
      (node (ref "R201") (pin "1") (pinfunction "1_1") (pintype "passive"))
      (node (ref "R205") (pin "2") (pinfunction "2_2") (pintype "passive"))
      (node (ref "TP27") (pin "1") (pintype "passive"))
    )
    (net (code "5") (name "5V_D") (class "Default")
      (node (ref "R163") (pin "1") (pinfunction "1_1") (pintype "passive"))
      (node (ref "R176") (pin "2") (pinfunction "2_2") (pintype "passive"))
      (node (ref "R183") (pin "1") (pinfunction "1_1") (pintype "passive"))
      (node (ref "TP33") (pin "1") (pintype "passive"))
    )
    (net (code "6") (name "10V") (class "Default")
      (node (ref "C105") (pin "1") (pinfunction "1_1") (pintype "passive"))
      (node (ref "C121") (pin "1") (pinfunction "1_1") (pintype "passive"))
      (node (ref "C137") (pin "1") (pinfunction "1_1") (pintype "passive"))
      (node (ref "C140") (pin "1") (pinfunction "1_1") (pintype "passive"))
      (node (ref "L4") (pin "2") (pinfunction "2_2") (pintype "passive"))
      (node (ref "R190") (pin "2") (pinfunction "2_2") (pintype "passive"))
      (node (ref "R191") (pin "2") (pinfunction "2_2") (pintype "passive"))
      (node (ref "TP32") (pin "1") (pintype "passive"))
      (node (ref "U22") (pin "4") (pinfunction "IN_4") (pintype "power_in"))
      (node (ref "U31") (pin "4") (pinfunction "IN_4") (pintype "power_in"))
    )
    (net (code "7") (name "10V_Gate") (class "Default")
      (node (ref "C113") (pin "1") (pinfunction "+_1") (pintype "passive"))
      (node (ref "C114") (pin "1") (pinfunction "1_1") (pintype "passive"))
      (node (ref "D9") (pin "1") (pinfunction "K_1") (pintype "passive"))
      (node (ref "L4") (pin "1") (pinfunction "1_1") (pintype "passive"))
      (node (ref "R209") (pin "1") (pinfunction "1_1") (pintype "passive"))
      (node (ref "R215") (pin "2") (pinfunction "2_2") (pintype "passive"))
      (node (ref "TP29") (pin "1") (pintype "passive"))
      (node (ref "U23") (pin "10") (pinfunction "VOUT_10") (pintype "output"))
    )
    (net (code "8") (name "12V_IN") (class "Default")
      (node (ref "C109") (pin "1") (pinfunction "+_1") (pintype "passive"))
      (node (ref "C110") (pin "1") (pinfunction "1_1") (pintype "passive"))
      (node (ref "C111") (pin "1") (pinfunction "1_1") (pintype "passive"))
      (node (ref "C157") (pin "1") (pinfunction "1_1") (pintype "passive"))
      (node (ref "C158") (pin "1") (pinfunction "1_1") (pintype "passive"))
      (node (ref "J4") (pin "1") (pinfunction "1_1") (pintype "passive"))
      (node (ref "L5") (pin "1") (pinfunction "1_1") (pintype "passive"))
      (node (ref "Q5") (pin "5") (pinfunction "D_5") (pintype "passive"))
      (node (ref "Q5") (pin "6") (pinfunction "D_6") (pintype "passive"))
      (node (ref "Q5") (pin "7") (pinfunction "D_7") (pintype "passive"))
      (node (ref "Q5") (pin "8") (pinfunction "D_8") (pintype "passive"))
      (node (ref "Q5") (pin "9") (pinfunction "D_9") (pintype "passive"))
      (node (ref "S3") (pin "1") (pinfunction "1_1") (pintype "passive"))
      (node (ref "TP28") (pin "1") (pintype "passive"))
      (node (ref "U23") (pin "1") (pinfunction "VIN_1") (pintype "power_in"))
    )
    (net (code "9") (name "12V_Out") (class "Default")
      (node (ref "S3") (pin "2") (pinfunction "2_2") (pintype "passive"))
    )
    (net (code "10") (name "AGND") (class "Default")
      (node (ref "C102") (pin "2") (pinfunction "2_2") (pintype "passive"))
      (node (ref "C103") (pin "2") (pinfunction "2_2") (pintype "passive"))
      (node (ref "C105") (pin "2") (pinfunction "2_2") (pintype "passive"))
      (node (ref "C108") (pin "2") (pinfunction "2_2") (pintype "passive"))
      (node (ref "C116") (pin "2") (pinfunction "2_2") (pintype "passive"))
      (node (ref "C117") (pin "2") (pinfunction "2_2") (pintype "passive"))
      (node (ref "C142") (pin "2") (pinfunction "2_2") (pintype "passive"))
      (node (ref "C146") (pin "2") (pinfunction "2_2") (pintype "passive"))
      (node (ref "C152") (pin "2") (pinfunction "2_2") (pintype "passive"))
      (node (ref "C153") (pin "2") (pinfunction "2_2") (pintype "passive"))
      (node (ref "C154") (pin "2") (pinfunction "2_2") (pintype "passive"))
      (node (ref "C155") (pin "2") (pinfunction "2_2") (pintype "passive"))
      (node (ref "C156") (pin "2") (pinfunction "-_2") (pintype "passive"))
      (node (ref "C157") (pin "2") (pinfunction "2_2") (pintype "passive"))
      (node (ref "C158") (pin "2") (pinfunction "2_2") (pintype "passive"))
      (node (ref "C159") (pin "1") (pinfunction "1_1") (pintype "passive"))
      (node (ref "C160") (pin "2") (pinfunction "2_2") (pintype "passive"))
      (node (ref "C161") (pin "2") (pinfunction "2_2") (pintype "passive"))
      (node (ref "C162") (pin "2") (pinfunction "2_2") (pintype "passive"))
      (node (ref "C164") (pin "2") (pinfunction "2_2") (pintype "passive"))
      (node (ref "D15") (pin "1") (pinfunction "K_1") (pintype "passive"))
      (node (ref "D17") (pin "1") (pinfunction "K_1") (pintype "passive"))
      (node (ref "J4") (pin "3") (pinfunction "3_3") (pintype "passive"))
      (node (ref "NT1") (pin "1") (pinfunction "1_1") (pintype "passive"))
      (node (ref "R199") (pin "1") (pinfunction "1_1") (pintype "passive"))
      (node (ref "R208") (pin "1") (pinfunction "1_1") (pintype "passive"))
      (node (ref "R210") (pin "1") (pinfunction "1_1") (pintype "passive"))
      (node (ref "R213") (pin "1") (pinfunction "1_1") (pintype "passive"))
      (node (ref "TP35") (pin "1") (pintype "passive"))
      (node (ref "U20") (pin "2") (pinfunction "GND_2") (pintype "power_in"))
      (node (ref "U21") (pin "10") (pinfunction "GND_10") (pintype "power_in"))
      (node (ref "U21") (pin "13") (pinfunction "PAD_13") (pintype "power_in"))
      (node (ref "U21") (pin "9") (pinfunction "GND_9") (pintype "power_in"))
      (node (ref "U22") (pin "5") (pinfunction "GND_5") (pintype "power_in"))
      (node (ref "U23") (pin "6") (pinfunction "AGND_6") (pintype "power_in"))
    )
    (net (code "11") (name "AVDD") (class "Default")
      (node (ref "C103") (pin "1") (pinfunction "1_1") (pintype "passive"))
      (node (ref "R180") (pin "1") (pinfunction "1_1") (pintype "passive"))
      (node (ref "R203") (pin "1") (pinfunction "1_1") (pintype "passive"))
      (node (ref "TP24") (pin "1") (pintype "passive"))
      (node (ref "U20") (pin "5") (pinfunction "VOUT_5") (pintype "power_in"))
    )
    (net (code "12") (name "DGND") (class "Default")
      (node (ref "C138") (pin "2") (pinfunction "2_2") (pintype "passive"))
      (node (ref "C139") (pin "2") (pinfunction "2_2") (pintype "passive"))
      (node (ref "C140") (pin "2") (pinfunction "2_2") (pintype "passive"))
      (node (ref "C141") (pin "2") (pinfunction "2_2") (pintype "passive"))
      (node (ref "C143") (pin "2") (pinfunction "2_2") (pintype "passive"))
      (node (ref "C163") (pin "2") (pinfunction "2_2") (pintype "passive"))
      (node (ref "C165") (pin "2") (pinfunction "2_2") (pintype "passive"))
      (node (ref "D14") (pin "1") (pinfunction "K_1") (pintype "passive"))
      (node (ref "D18") (pin "1") (pinfunction "K_1") (pintype "passive"))
      (node (ref "TP36") (pin "1") (pintype "passive"))
      (node (ref "U25") (pin "2") (pinfunction "GND_2") (pintype "power_in"))
      (node (ref "U31") (pin "5") (pinfunction "GND_5") (pintype "power_in"))
    )
    (net (code "13") (name "DVDD") (class "Default")
      (node (ref "C163") (pin "1") (pinfunction "1_1") (pintype "passive"))
      (node (ref "R179") (pin "1") (pinfunction "1_1") (pintype "passive"))
      (node (ref "R194") (pin "1") (pinfunction "1_1") (pintype "passive"))
      (node (ref "R203") (pin "2") (pinfunction "2_2") (pintype "passive"))
      (node (ref "TP25") (pin "1") (pintype "passive"))
      (node (ref "U25") (pin "5") (pinfunction "OUT_5") (pintype "power_in"))
    )
    (net (code "14") (name "Net-(C120-Pad2)") (class "Default")
      (node (ref "C120") (pin "2") (pinfunction "2_2") (pintype "passive"))
      (node (ref "R212") (pin "2") (pinfunction "2_2") (pintype "passive"))
    )
    (net (code "15") (name "Net-(C156-+)") (class "Default")
      (node (ref "C152") (pin "1") (pinfunction "1_1") (pintype "passive"))
      (node (ref "C153") (pin "1") (pinfunction "1_1") (pintype "passive"))
      (node (ref "C154") (pin "1") (pinfunction "1_1") (pintype "passive"))
      (node (ref "C155") (pin "1") (pinfunction "1_1") (pintype "passive"))
      (node (ref "C156") (pin "1") (pinfunction "+_1") (pintype "passive"))
      (node (ref "L5") (pin "2") (pinfunction "2_2") (pintype "passive"))
      (node (ref "R195") (pin "1") (pinfunction "1_1") (pintype "passive"))
      (node (ref "U21") (pin "12") (pinfunction "VIN_12") (pintype "power_in"))
    )
    (net (code "16") (name "Net-(D9-A)") (class "Default")
      (node (ref "D9") (pin "2") (pinfunction "A_2") (pintype "passive"))
      (node (ref "L3") (pin "2") (pinfunction "2_2") (pintype "passive"))
      (node (ref "Q6") (pin "5") (pinfunction "D_5") (pintype "passive"))
      (node (ref "Q6") (pin "6") (pinfunction "D_6") (pintype "passive"))
      (node (ref "Q6") (pin "7") (pinfunction "D_7") (pintype "passive"))
      (node (ref "Q6") (pin "8") (pinfunction "D_8") (pintype "passive"))
      (node (ref "Q6") (pin "9") (pinfunction "D_9") (pintype "passive"))
    )
    (net (code "17") (name "Net-(D10-A)") (class "Default")
      (node (ref "D10") (pin "2") (pinfunction "A_2") (pintype "passive"))
      (node (ref "R211") (pin "2") (pinfunction "2_2") (pintype "passive"))
      (node (ref "U23") (pin "12") (pinfunction "CS_12") (pintype "input"))
    )
    (net (code "18") (name "Net-(D10-K)") (class "Default")
      (node (ref "C112") (pin "1") (pinfunction "1_1") (pintype "passive"))
      (node (ref "D10") (pin "1") (pinfunction "K_1") (pintype "passive"))
      (node (ref "L3") (pin "1") (pinfunction "1_1") (pintype "passive"))
      (node (ref "Q5") (pin "1") (pinfunction "S_1") (pintype "passive"))
      (node (ref "Q5") (pin "2") (pinfunction "S_2") (pintype "passive"))
      (node (ref "Q5") (pin "3") (pinfunction "S_3") (pintype "passive"))
      (node (ref "U23") (pin "20") (pinfunction "HS_20") (pintype "input"))
    )
    (net (code "19") (name "Net-(D11-A)") (class "Default")
      (node (ref "D11") (pin "2") (pinfunction "A_2") (pintype "passive"))
      (node (ref "R209") (pin "2") (pinfunction "2_2") (pintype "passive"))
    )
    (net (code "20") (name "Net-(D14-A)") (class "Default")
      (node (ref "D14") (pin "2") (pinfunction "A_2") (pintype "passive"))
      (node (ref "R179") (pin "2") (pinfunction "2_2") (pintype "passive"))
    )
    (net (code "21") (name "Net-(D15-A)") (class "Default")
      (node (ref "D15") (pin "2") (pinfunction "A_2") (pintype "passive"))
      (node (ref "R180") (pin "2") (pinfunction "2_2") (pintype "passive"))
    )
    (net (code "22") (name "Net-(D17-A)") (class "Default")
      (node (ref "D17") (pin "2") (pinfunction "A_2") (pintype "passive"))
      (node (ref "R182") (pin "2") (pinfunction "2_2") (pintype "passive"))
    )
    (net (code "23") (name "Net-(D18-A)") (class "Default")
      (node (ref "D18") (pin "2") (pinfunction "A_2") (pintype "passive"))
      (node (ref "R183") (pin "2") (pinfunction "2_2") (pintype "passive"))
    )
    (net (code "24") (name "Net-(J4-Pad2)") (class "Default")
      (node (ref "J4") (pin "2") (pinfunction "2_2") (pintype "passive"))
      (node (ref "R207") (pin "2") (pinfunction "2_2") (pintype "passive"))
    )
    (net (code "25") (name "Net-(Q5-G)") (class "Default")
      (node (ref "Q5") (pin "4") (pinfunction "G_4") (pintype "passive"))
      (node (ref "U23") (pin "19") (pinfunction "HO_19") (pintype "output"))
    )
    (net (code "26") (name "Net-(Q6-G)") (class "Default")
      (node (ref "Q6") (pin "4") (pinfunction "G_4") (pintype "passive"))
      (node (ref "U23") (pin "15") (pinfunction "LO_15") (pintype "output"))
    )
    (net (code "27") (name "Net-(R214-Pad2)") (class "Default")
      (node (ref "R214") (pin "2") (pinfunction "2_2") (pintype "passive"))
      (node (ref "R215") (pin "1") (pinfunction "1_1") (pintype "passive"))
    )
    (net (code "28") (name "Net-(U20-EN)") (class "Default")
      (node (ref "C146") (pin "1") (pinfunction "1_1") (pintype "passive"))
      (node (ref "R194") (pin "2") (pinfunction "2_2") (pintype "passive"))
      (node (ref "R202") (pin "1") (pinfunction "1_1") (pintype "passive"))
      (node (ref "U20") (pin "3") (pinfunction "EN_3") (pintype "input"))
    )
    (net (code "29") (name "Net-(U20-VIN)") (class "Default")
      (node (ref "C102") (pin "1") (pinfunction "1_1") (pintype "passive"))
      (node (ref "R201") (pin "2") (pinfunction "2_2") (pintype "passive"))
      (node (ref "R202") (pin "2") (pinfunction "2_2") (pintype "passive"))
      (node (ref "U20") (pin "1") (pinfunction "VIN_1") (pintype "power_in"))
    )
    (net (code "30") (name "Net-(U21-CAP)") (class "Default")
      (node (ref "C159") (pin "2") (pinfunction "2_2") (pintype "passive"))
      (node (ref "U21") (pin "6") (pinfunction "CAP_6") (pintype "passive"))
    )
    (net (code "31") (name "Net-(U21-CP)") (class "Default")
      (node (ref "C104") (pin "1") (pinfunction "1_1") (pintype "passive"))
      (node (ref "C106") (pin "1") (pinfunction "1_1") (pintype "passive"))
      (node (ref "C107") (pin "1") (pinfunction "1_1") (pintype "passive"))
      (node (ref "U21") (pin "11") (pinfunction "CP_11") (pintype "passive"))
    )
    (net (code "32") (name "Net-(U21-EN)") (class "Default")
      (node (ref "R195") (pin "2") (pinfunction "2_2") (pintype "passive"))
      (node (ref "U21") (pin "2") (pinfunction "EN_2") (pintype "input"))
    )
    (net (code "33") (name "Net-(U21-FB)") (class "Default")
      (node (ref "R197") (pin "1") (pinfunction "1_1") (pintype "passive"))
      (node (ref "R199") (pin "2") (pinfunction "2_2") (pintype "passive"))
      (node (ref "U21") (pin "5") (pinfunction "FB_5") (pintype "input"))
    )
    (net (code "34") (name "Net-(U21-SW)") (class "Default")
      (node (ref "C104") (pin "2") (pinfunction "2_2") (pintype "passive"))
      (node (ref "C106") (pin "2") (pinfunction "2_2") (pintype "passive"))
      (node (ref "C107") (pin "2") (pinfunction "2_2") (pintype "passive"))
      (node (ref "L6") (pin "1") (pinfunction "1_1") (pintype "passive"))
      (node (ref "U21") (pin "8") (pinfunction "SW_8") (pintype "power_in"))
    )
    (net (code "35") (name "Net-(U21-VAUX)") (class "Default")
      (node (ref "C164") (pin "1") (pinfunction "1_1") (pintype "passive"))
      (node (ref "R198") (pin "2") (pinfunction "2_2") (pintype "passive"))
      (node (ref "U21") (pin "1") (pinfunction "VAUX_1") (pintype "input"))
    )
    (net (code "36") (name "Net-(U21-VOUT)") (class "Default")
      (node (ref "R196") (pin "2") (pinfunction "2_2") (pintype "passive"))
      (node (ref "U21") (pin "7") (pinfunction "VOUT_7") (pintype "input"))
    )
    (net (code "37") (name "Net-(U21-VREF)") (class "Default")
      (node (ref "R197") (pin "2") (pinfunction "2_2") (pintype "passive"))
      (node (ref "U21") (pin "4") (pinfunction "VREF_4") (pintype "output"))
    )
    (net (code "38") (name "Net-(U22-EN)") (class "Default")
      (node (ref "C142") (pin "1") (pinfunction "1_1") (pintype "passive"))
      (node (ref "R188") (pin "2") (pinfunction "2_2") (pintype "passive"))
      (node (ref "R190") (pin "1") (pinfunction "1_1") (pintype "passive"))
      (node (ref "U22") (pin "1") (pinfunction "EN_1") (pintype "input"))
    )
    (net (code "39") (name "Net-(U22-OUT)") (class "Default")
      (node (ref "C108") (pin "1") (pinfunction "1_1") (pintype "passive"))
      (node (ref "R205") (pin "1") (pinfunction "1_1") (pintype "passive"))
      (node (ref "U22") (pin "3") (pinfunction "OUT_3") (pintype "power_in"))
    )
    (net (code "40") (name "Net-(U23-COMP)") (class "Default")
      (node (ref "C115") (pin "1") (pinfunction "1_1") (pintype "passive"))
      (node (ref "C120") (pin "1") (pinfunction "1_1") (pintype "passive"))
      (node (ref "U23") (pin "9") (pinfunction "COMP_9") (pintype "output"))
    )
    (net (code "41") (name "Net-(U23-FB)") (class "Default")
      (node (ref "C115") (pin "2") (pinfunction "2_2") (pintype "passive"))
      (node (ref "R212") (pin "1") (pinfunction "1_1") (pintype "passive"))
      (node (ref "R213") (pin "2") (pinfunction "2_2") (pintype "passive"))
      (node (ref "R214") (pin "1") (pinfunction "1_1") (pintype "passive"))
      (node (ref "U23") (pin "8") (pinfunction "FB_8") (pintype "input"))
    )
    (net (code "42") (name "Net-(U23-HB)") (class "Default")
      (node (ref "C112") (pin "2") (pinfunction "2_2") (pintype "passive"))
      (node (ref "U23") (pin "18") (pinfunction "HB_18") (pintype "input"))
    )
    (net (code "43") (name "Net-(U23-RAMP)") (class "Default")
      (node (ref "C117") (pin "1") (pinfunction "1_1") (pintype "passive"))
      (node (ref "U23") (pin "5") (pinfunction "RAMP_5") (pintype "input"))
    )
    (net (code "44") (name "Net-(U23-RT)") (class "Default")
      (node (ref "R210") (pin "2") (pinfunction "2_2") (pintype "passive"))
      (node (ref "U23") (pin "3") (pinfunction "RT_3") (pintype "input"))
    )
    (net (code "45") (name "Net-(U23-SS)") (class "Default")
      (node (ref "C116") (pin "1") (pinfunction "1_1") (pintype "passive"))
      (node (ref "U23") (pin "7") (pinfunction "SS_7") (pintype "input"))
    )
    (net (code "46") (name "Net-(U23-UVLO)") (class "Default")
      (node (ref "R206") (pin "2") (pinfunction "2_2") (pintype "passive"))
      (node (ref "U23") (pin "2") (pinfunction "UVLO_2") (pintype "input"))
    )
    (net (code "47") (name "Net-(U23-VCC)") (class "Default")
      (node (ref "C119") (pin "1") (pinfunction "1_1") (pintype "passive"))
      (node (ref "U23") (pin "16") (pinfunction "VCC_16") (pintype "power_in"))
    )
    (net (code "48") (name "Net-(U23-VCCX)") (class "Default")
      (node (ref "C118") (pin "1") (pinfunction "1_1") (pintype "passive"))
      (node (ref "U23") (pin "17") (pinfunction "VCCX_17") (pintype "power_in"))
    )
    (net (code "49") (name "Net-(U25-EN)") (class "Default")
      (node (ref "C138") (pin "1") (pinfunction "1_1") (pintype "passive"))
      (node (ref "C139") (pin "1") (pinfunction "1_1") (pintype "passive"))
      (node (ref "R163") (pin "2") (pinfunction "2_2") (pintype "passive"))
      (node (ref "U25") (pin "1") (pinfunction "IN_1") (pintype "power_in"))
      (node (ref "U25") (pin "3") (pinfunction "EN_3") (pintype "input"))
    )
    (net (code "50") (name "Net-(U25-NR{slash}FB)") (class "Default")
      (node (ref "C165") (pin "1") (pinfunction "1_1") (pintype "passive"))
      (node (ref "U25") (pin "4") (pinfunction "NR/FB_4") (pintype "input"))
    )
    (net (code "51") (name "Net-(U31-EN)") (class "Default")
      (node (ref "C143") (pin "1") (pinfunction "1_1") (pintype "passive"))
      (node (ref "R189") (pin "2") (pinfunction "2_2") (pintype "passive"))
      (node (ref "R191") (pin "1") (pinfunction "1_1") (pintype "passive"))
      (node (ref "U31") (pin "1") (pinfunction "EN_1") (pintype "input"))
    )
    (net (code "52") (name "Net-(U31-OUT)") (class "Default")
      (node (ref "C141") (pin "1") (pinfunction "1_1") (pintype "passive"))
      (node (ref "R176") (pin "1") (pinfunction "1_1") (pintype "passive"))
      (node (ref "U31") (pin "3") (pinfunction "OUT_3") (pintype "power_in"))
    )
    (net (code "53") (name "PGND") (class "Default")
      (node (ref "C109") (pin "2") (pinfunction "-_2") (pintype "passive"))
      (node (ref "C110") (pin "2") (pinfunction "2_2") (pintype "passive"))
      (node (ref "C111") (pin "2") (pinfunction "2_2") (pintype "passive"))
      (node (ref "C113") (pin "2") (pinfunction "-_2") (pintype "passive"))
      (node (ref "C114") (pin "2") (pinfunction "2_2") (pintype "passive"))
      (node (ref "C118") (pin "2") (pinfunction "2_2") (pintype "passive"))
      (node (ref "C119") (pin "2") (pinfunction "2_2") (pintype "passive"))
      (node (ref "C121") (pin "2") (pinfunction "2_2") (pintype "passive"))
      (node (ref "C137") (pin "2") (pinfunction "2_2") (pintype "passive"))
      (node (ref "D11") (pin "1") (pinfunction "K_1") (pintype "passive"))
      (node (ref "NT1") (pin "2") (pinfunction "2_2") (pintype "passive"))
      (node (ref "Q6") (pin "1") (pinfunction "S_1") (pintype "passive"))
      (node (ref "Q6") (pin "2") (pinfunction "S_2") (pintype "passive"))
      (node (ref "Q6") (pin "3") (pinfunction "S_3") (pintype "passive"))
      (node (ref "R211") (pin "1") (pinfunction "1_1") (pintype "passive"))
      (node (ref "TP34") (pin "1") (pintype "passive"))
      (node (ref "U23") (pin "13") (pinfunction "CSG_13") (pintype "input"))
      (node (ref "U23") (pin "14") (pinfunction "PGND_14") (pintype "power_in"))
      (node (ref "U23") (pin "21") (pinfunction "EP_21") (pintype "power_in"))
    )
    (net (code "54") (name "unconnected-(U20-N{slash}C-Pad4)") (class "Default")
      (node (ref "U20") (pin "4") (pinfunction "N/C_4") (pintype "passive"))
    )
    (net (code "55") (name "unconnected-(U22-NC-Pad2)") (class "Default")
      (node (ref "U22") (pin "2") (pinfunction "NC_2") (pintype "passive+no_connect"))
    )
    (net (code "56") (name "unconnected-(U23-SYNC-Pad11)") (class "Default")
      (node (ref "U23") (pin "11") (pinfunction "SYNC_11") (pintype "input"))
    )
    (net (code "57") (name "unconnected-(U31-NC-Pad2)") (class "Default")
      (node (ref "U31") (pin "2") (pinfunction "NC_2") (pintype "passive+no_connect"))
    )
  )
)
